# Att_steet_1.net
KiCad netlist of a schematic drawn in Altium Designer
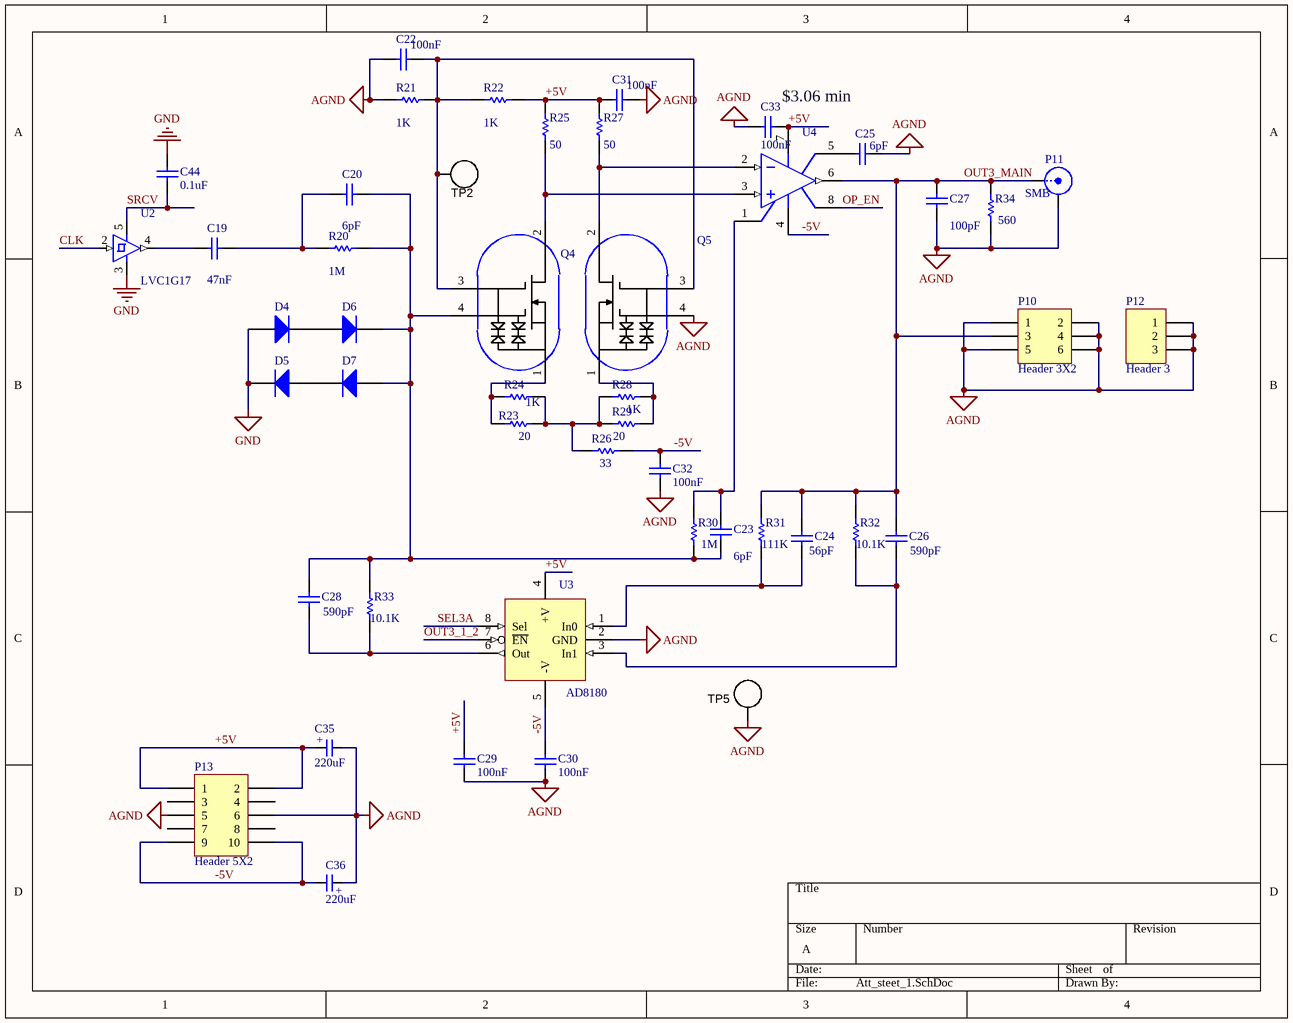
[diagram p0: Att_steet_1.SchDoc]

(export (version "E")
  (design (tool "Eeschema 10.0.6"))
  (components
    (comp (ref "C19")
      (value "47nF")
      (footprint "0805")
      (description "Ceramic Chip Capacitor - Standard")
      (fields (field (name "Comment") "C0805") (field (name "PUBLISHER") "Altium Limited"))
      (libsource (lib "KEMET Chip Capacitor") (part "C0805"))
    )
    (comp (ref "C20")
      (value "6pF")
      (footprint "0805")
      (description "Ceramic Chip Capacitor - Standard")
      (fields (field (name "Comment") "C0805") (field (name "PUBLISHER") "Altium Limited"))
      (libsource (lib "KEMET Chip Capacitor") (part "C0805"))
    )
    (comp (ref "C22")
      (value "100nF")
      (footprint "0805")
      (description "Ceramic Chip Capacitor - Standard")
      (fields (field (name "Comment") "C0805") (field (name "PUBLISHER") "Altium Limited"))
      (libsource (lib "KEMET Chip Capacitor") (part "C0805"))
    )
    (comp (ref "C23")
      (value "6pF")
      (footprint "0805")
      (description "Ceramic Chip Capacitor - Standard")
      (fields (field (name "Comment") "C0805") (field (name "PUBLISHER") "Altium Limited"))
      (libsource (lib "KEMET Chip Capacitor") (part "C0805"))
    )
    (comp (ref "C24")
      (value "56pF")
      (footprint "0805")
      (description "Ceramic Chip Capacitor - Standard")
      (fields (field (name "Comment") "C0805") (field (name "PUBLISHER") "Altium Limited"))
      (libsource (lib "KEMET Chip Capacitor") (part "C0805"))
    )
    (comp (ref "C25")
      (value "6pF")
      (footprint "C0805")
      (description "Capacitor (Semiconductor SIM Model)")
      (fields (field (name "Comment") "Cap Semi") (field (name "PUBLISHER") "Altium Limited"))
      (libsource (lib "Miscellaneous Devices") (part "Cap Semi"))
    )
    (comp (ref "C26")
      (value "590pF")
      (footprint "0805")
      (description "Ceramic Chip Capacitor - Standard")
      (fields (field (name "Comment") "C0805") (field (name "PUBLISHER") "Altium Limited"))
      (libsource (lib "KEMET Chip Capacitor") (part "C0805"))
    )
    (comp (ref "C27")
      (value "100pF")
      (footprint "0805")
      (description "Ceramic Chip Capacitor - Standard")
      (fields (field (name "Comment") "C0805") (field (name "PUBLISHER") "Altium Limited"))
      (libsource (lib "KEMET Chip Capacitor") (part "C0805"))
    )
    (comp (ref "C28")
      (value "590pF")
      (footprint "0805")
      (description "Ceramic Chip Capacitor - Standard")
      (fields (field (name "Comment") "C0805") (field (name "PUBLISHER") "Altium Limited"))
      (libsource (lib "KEMET Chip Capacitor") (part "C0805"))
    )
    (comp (ref "C29")
      (value "100nF")
      (footprint "0805")
      (description "Ceramic Chip Capacitor - Standard")
      (fields (field (name "Comment") "C0805") (field (name "PUBLISHER") "Altium Limited"))
      (libsource (lib "KEMET Chip Capacitor") (part "C0805"))
    )
    (comp (ref "C30")
      (value "100nF")
      (footprint "0805")
      (description "Ceramic Chip Capacitor - Standard")
      (fields (field (name "Comment") "C0805") (field (name "PUBLISHER") "Altium Limited"))
      (libsource (lib "KEMET Chip Capacitor") (part "C0805"))
    )
    (comp (ref "C31")
      (value "100nF")
      (footprint "0805")
      (description "Ceramic Chip Capacitor - Standard")
      (fields (field (name "Comment") "C0805") (field (name "PUBLISHER") "Altium Limited"))
      (libsource (lib "KEMET Chip Capacitor") (part "C0805"))
    )
    (comp (ref "C32")
      (value "100nF")
      (footprint "0805")
      (description "Ceramic Chip Capacitor - Standard")
      (fields (field (name "Comment") "C0805") (field (name "PUBLISHER") "Altium Limited"))
      (libsource (lib "KEMET Chip Capacitor") (part "C0805"))
    )
    (comp (ref "C33")
      (value "100nF")
      (footprint "0805")
      (description "Ceramic Chip Capacitor - Standard")
      (fields (field (name "Comment") "C0805") (field (name "PUBLISHER") "Altium Limited"))
      (libsource (lib "KEMET Chip Capacitor") (part "C0805"))
    )
    (comp (ref "C35")
      (value "220uF")
      (footprint "Scope:H13")
      (fields (field (name "MANUFACTURER") "Panasonic") (field (name "Comment") "Cap"))
      (libsource (lib "Scope") (part "Lyt Cap"))
    )
    (comp (ref "C36")
      (value "220uF")
      (footprint "Scope:H13")
      (fields (field (name "MANUFACTURER") "Panasonic") (field (name "Comment") "Cap"))
      (libsource (lib "Scope") (part "Lyt Cap"))
    )
    (comp (ref "C44")
      (value "0.1uF")
      (footprint "C0805")
      (description "Capacitor")
      (fields (field (name "Comment") "Cap") (field (name "PUBLISHER") "Altium Limited"))
      (libsource (lib "Miscellaneous Devices") (part "Cap"))
    )
    (comp (ref "D4")
      (value "Diode BAS21")
      (footprint "SOT95P240-3N")
      (description "Silicon Switching Diode for High-Speed, High-Voltage Switching")
      (fields (field (name "PUBLISHER") "Altium Limited"))
      (libsource (lib "Miscellaneous Devices") (part "Diode BAS21"))
    )
    (comp (ref "D5")
      (value "Diode BAS21")
      (footprint "SOT95P240-3N")
      (description "Silicon Switching Diode for High-Speed, High-Voltage Switching")
      (fields (field (name "PUBLISHER") "Altium Limited"))
      (libsource (lib "Miscellaneous Devices") (part "Diode BAS21"))
    )
    (comp (ref "D6")
      (value "Diode BAS21")
      (footprint "SOT95P240-3N")
      (description "Silicon Switching Diode for High-Speed, High-Voltage Switching")
      (fields (field (name "PUBLISHER") "Altium Limited"))
      (libsource (lib "Miscellaneous Devices") (part "Diode BAS21"))
    )
    (comp (ref "D7")
      (value "Diode BAS21")
      (footprint "SOT95P240-3N")
      (description "Silicon Switching Diode for High-Speed, High-Voltage Switching")
      (fields (field (name "PUBLISHER") "Altium Limited"))
      (libsource (lib "Miscellaneous Devices") (part "Diode BAS21"))
    )
    (comp (ref "P10")
      (value "Header 3X2")
      (footprint "HDR2X3")
      (description "Header, 3-Pin, Dual row")
      (fields (field (name "PUBLISHER") "Altium Limited"))
      (libsource (lib "Miscellaneous Connectors") (part "Header 3X2"))
    )
    (comp (ref "P11")
      (value "SMB")
      (footprint "SMB_V-RJ45")
      (description "SMB Straight Connector")
      (fields (field (name "PUBLISHER") "Altium Limited"))
      (libsource (lib "Miscellaneous Connectors") (part "SMB"))
    )
    (comp (ref "P12")
      (value "Header 3")
      (footprint "HDR1X3")
      (description "Header, 3-Pin")
      (fields (field (name "PUBLISHER") "Altium Limited"))
      (libsource (lib "Miscellaneous Connectors") (part "Header 3"))
    )
    (comp (ref "P13")
      (value "Header 5X2")
      (footprint "HDR2X5")
      (description "Header, 5-Pin, Dual row")
      (fields (field (name "PUBLISHER") "Altium Limited"))
      (libsource (lib "Miscellaneous Connectors") (part "Header 5X2"))
    )
    (comp (ref "Q4")
      (value "MOSFET")
      (footprint "Scope:SOT143")
      (description "Dual-gate MOSFET")
      (fields (field (name "MANUFACTURER") "NXP"))
      (libsource (lib "") (part "BF998_1"))
    )
    (comp (ref "Q5")
      (value "MOSFET")
      (footprint "Scope:SOT143")
      (description "Dual-gate MOSFET")
      (fields (field (name "MANUFACTURER") "NXP"))
      (libsource (lib "Scope") (part "BF998"))
    )
    (comp (ref "R20")
      (value "1M")
      (footprint "0805")
      (fields (field (name "Comment") "ERA6Y") (field (name "PUBLISHER") "Altium Limited"))
      (libsource (lib "Panasonic Resistor") (part "ERA6Y"))
    )
    (comp (ref "R21")
      (value "1K")
      (footprint "0805")
      (fields (field (name "Comment") "ERA6Y") (field (name "PUBLISHER") "Altium Limited"))
      (libsource (lib "Panasonic Resistor") (part "ERA6Y"))
    )
    (comp (ref "R22")
      (value "1K")
      (footprint "0805")
      (fields (field (name "Comment") "ERA6Y") (field (name "PUBLISHER") "Altium Limited"))
      (libsource (lib "Panasonic Resistor") (part "ERA6Y"))
    )
    (comp (ref "R23")
      (value "20")
      (footprint "0805")
      (fields (field (name "Comment") "ERA6Y") (field (name "PUBLISHER") "Altium Limited"))
      (libsource (lib "Panasonic Resistor") (part "ERA6Y"))
    )
    (comp (ref "R24")
      (value "1K")
      (footprint "0805")
      (fields (field (name "Comment") "ERA6Y") (field (name "PUBLISHER") "Altium Limited"))
      (libsource (lib "Panasonic Resistor") (part "ERA6Y"))
    )
    (comp (ref "R25")
      (value "50")
      (footprint "0805")
      (fields (field (name "Comment") "ERA6Y") (field (name "PUBLISHER") "Altium Limited"))
      (libsource (lib "Panasonic Resistor") (part "ERA6Y"))
    )
    (comp (ref "R26")
      (value "33")
      (footprint "0805")
      (fields (field (name "Comment") "ERA6Y") (field (name "PUBLISHER") "Altium Limited"))
      (libsource (lib "Panasonic Resistor") (part "ERA6Y"))
    )
    (comp (ref "R27")
      (value "50")
      (footprint "0805")
      (fields (field (name "Comment") "ERA6Y") (field (name "PUBLISHER") "Altium Limited"))
      (libsource (lib "Panasonic Resistor") (part "ERA6Y"))
    )
    (comp (ref "R28")
      (value "1K")
      (footprint "0805")
      (fields (field (name "Comment") "ERA6Y") (field (name "PUBLISHER") "Altium Limited"))
      (libsource (lib "Panasonic Resistor") (part "ERA6Y"))
    )
    (comp (ref "R29")
      (value "20")
      (footprint "0805")
      (fields (field (name "Comment") "ERA6Y") (field (name "PUBLISHER") "Altium Limited"))
      (libsource (lib "Panasonic Resistor") (part "ERA6Y"))
    )
    (comp (ref "R30")
      (value "1M")
      (footprint "0805")
      (fields (field (name "Comment") "ERA6Y") (field (name "PUBLISHER") "Altium Limited"))
      (libsource (lib "Panasonic Resistor") (part "ERA6Y"))
    )
    (comp (ref "R31")
      (value "111K")
      (footprint "0805")
      (fields (field (name "Comment") "ERA6Y") (field (name "PUBLISHER") "Altium Limited"))
      (libsource (lib "Panasonic Resistor") (part "ERA6Y"))
    )
    (comp (ref "R32")
      (value "10.1K")
      (footprint "0805")
      (fields (field (name "Comment") "ERA6Y") (field (name "PUBLISHER") "Altium Limited"))
      (libsource (lib "Panasonic Resistor") (part "ERA6Y"))
    )
    (comp (ref "R33")
      (value "10.1K")
      (footprint "0805")
      (fields (field (name "Comment") "ERA6Y") (field (name "PUBLISHER") "Altium Limited"))
      (libsource (lib "Panasonic Resistor") (part "ERA6Y"))
    )
    (comp (ref "R34")
      (value "560")
      (footprint "0805")
      (fields (field (name "Comment") "ERA6Y") (field (name "PUBLISHER") "Altium Limited"))
      (libsource (lib "Panasonic Resistor") (part "ERA6Y"))
    )
    (comp (ref "TP2")
      (value "TESTPOINT")
      (footprint "TESTPOINT")
      (description "TEST POINT.  No entry in BOM.")
      (libsource (lib "NSC MiscParts") (part "TESTPOINT"))
    )
    (comp (ref "TP5")
      (value "TESTPOINT")
      (footprint "TESTPOINT")
      (description "TEST POINT.  No entry in BOM.")
      (libsource (lib "NSC MiscParts") (part "TESTPOINT"))
    )
    (comp (ref "U2")
      (value "LVC1G17")
      (footprint "SC_70_5")
      (fields
        (field (name "MANUFACTURER") "Texas Instruments")
        (field (name "MANUFACTURER PART NUMBER") "SN74LVC1G17DCKR")
        (field (name "Comment") "SN74LVC1G17")
      )
      (libsource (lib "VIVENG_Library") (part "SN74LVC1G17"))
    )
    (comp (ref "U3")
      (value "AD8180")
      (footprint "SOIC127P600-8AL")
      (fields (field (name "PARTNUMBER") "AD8180"))
      (libsource (lib "Scope") (part "AD8180"))
    )
    (comp (ref "U4")
      (value "AD707AR")
      (footprint "SO-8_N")
      (description "Ultra-Low Drift Operational Amplifier")
      (fields (field (name "PARTNUMBER") "AD8099") (field (name "PUBLISHER") "Altium Limited"))
      (libsource (lib "AD Operational Amplifier") (part "AD707AR"))
    )
  )
  (nets
    (net (code "1") (name "/+5V") (class "Default")
      (node (ref "C29") (pin "1") (pinfunction "1_1") (pintype "passive"))
      (node (ref "C31") (pin "1") (pinfunction "1_1") (pintype "passive"))
      (node (ref "C33") (pin "1") (pinfunction "1_1") (pintype "passive"))
      (node (ref "C35") (pin "1") (pinfunction "1_1") (pintype "passive"))
      (node (ref "P13") (pin "1") (pinfunction "1_1") (pintype "passive"))
      (node (ref "P13") (pin "2") (pinfunction "2_2") (pintype "passive"))
      (node (ref "R22") (pin "1") (pinfunction "1_1") (pintype "passive"))
      (node (ref "R25") (pin "1") (pinfunction "1_1") (pintype "passive"))
      (node (ref "R27") (pin "1") (pinfunction "1_1") (pintype "passive"))
      (node (ref "U3") (pin "4") (pinfunction "+V_4") (pintype "power_in"))
      (node (ref "U4") (pin "7") (pinfunction "V+_7") (pintype "power_in"))
    )
    (net (code "2") (name "/-5V") (class "Default")
      (node (ref "C30") (pin "1") (pinfunction "1_1") (pintype "passive"))
      (node (ref "C32") (pin "2") (pinfunction "2_2") (pintype "passive"))
      (node (ref "C36") (pin "2") (pinfunction "2_2") (pintype "passive"))
      (node (ref "P13") (pin "10") (pinfunction "10_10") (pintype "passive"))
      (node (ref "P13") (pin "9") (pinfunction "9_9") (pintype "passive"))
      (node (ref "R26") (pin "1") (pinfunction "1_1") (pintype "passive"))
      (node (ref "U3") (pin "5") (pinfunction "-V_5") (pintype "power_in"))
      (node (ref "U4") (pin "4") (pinfunction "V-_4") (pintype "power_in"))
    )
    (net (code "3") (name "/CLK") (class "Default")
      (node (ref "U2") (pin "2") (pinfunction "1A_2") (pintype "input"))
    )
    (net (code "4") (name "/OP_EN") (class "Default")
      (node (ref "U4") (pin "8") (pinfunction "NULL2_8") (pintype "passive"))
    )
    (net (code "5") (name "/OUT3_1_2") (class "Default")
      (node (ref "U3") (pin "7") (pinfunction "~{EN}_7") (pintype "input"))
    )
    (net (code "6") (name "/OUT3_MAIN") (class "Default")
      (node (ref "C24") (pin "2") (pinfunction "2_2") (pintype "passive"))
      (node (ref "C26") (pin "2") (pinfunction "2_2") (pintype "passive"))
      (node (ref "C27") (pin "2") (pinfunction "2_2") (pintype "passive"))
      (node (ref "P10") (pin "3") (pinfunction "3_3") (pintype "passive"))
      (node (ref "P11") (pin "1") (pinfunction "X_1") (pintype "passive"))
      (node (ref "R31") (pin "2") (pinfunction "2_2") (pintype "passive"))
      (node (ref "R32") (pin "2") (pinfunction "2_2") (pintype "passive"))
      (node (ref "R34") (pin "2") (pinfunction "2_2") (pintype "passive"))
      (node (ref "U4") (pin "6") (pinfunction "OUT_6") (pintype "output"))
    )
    (net (code "7") (name "/SEL3A") (class "Default")
      (node (ref "U3") (pin "8") (pinfunction "Sel_8") (pintype "input"))
    )
    (net (code "8") (name "/SRCV") (class "Default")
      (node (ref "C44") (pin "1") (pinfunction "1_1") (pintype "passive"))
      (node (ref "U2") (pin "5") (pinfunction "VCC_5") (pintype "power_in"))
    )
    (net (code "9") (name "AGND") (class "Default")
      (node (ref "C22") (pin "1") (pinfunction "1_1") (pintype "passive"))
      (node (ref "C25") (pin "2") (pinfunction "2_2") (pintype "passive"))
      (node (ref "C27") (pin "1") (pinfunction "1_1") (pintype "passive"))
      (node (ref "C29") (pin "2") (pinfunction "2_2") (pintype "passive"))
      (node (ref "C30") (pin "2") (pinfunction "2_2") (pintype "passive"))
      (node (ref "C31") (pin "2") (pinfunction "2_2") (pintype "passive"))
      (node (ref "C32") (pin "1") (pinfunction "1_1") (pintype "passive"))
      (node (ref "C33") (pin "2") (pinfunction "2_2") (pintype "passive"))
      (node (ref "C35") (pin "2") (pinfunction "2_2") (pintype "passive"))
      (node (ref "C36") (pin "1") (pinfunction "1_1") (pintype "passive"))
      (node (ref "P10") (pin "1") (pinfunction "1_1") (pintype "passive"))
      (node (ref "P10") (pin "2") (pinfunction "2_2") (pintype "passive"))
      (node (ref "P10") (pin "4") (pinfunction "4_4") (pintype "passive"))
      (node (ref "P10") (pin "5") (pinfunction "5_5") (pintype "passive"))
      (node (ref "P10") (pin "6") (pinfunction "6_6") (pintype "passive"))
      (node (ref "P11") (pin "2") (pinfunction "Y_2") (pintype "passive"))
      (node (ref "P12") (pin "1") (pinfunction "1_1") (pintype "passive"))
      (node (ref "P12") (pin "2") (pinfunction "2_2") (pintype "passive"))
      (node (ref "P12") (pin "3") (pinfunction "3_3") (pintype "passive"))
      (node (ref "P13") (pin "5") (pinfunction "5_5") (pintype "passive"))
      (node (ref "P13") (pin "6") (pinfunction "6_6") (pintype "passive"))
      (node (ref "Q5") (pin "4") (pinfunction "4_4") (pintype "passive"))
      (node (ref "R21") (pin "2") (pinfunction "2_2") (pintype "passive"))
      (node (ref "R34") (pin "1") (pinfunction "1_1") (pintype "passive"))
      (node (ref "TP5") (pin "1") (pintype "passive"))
      (node (ref "U3") (pin "2") (pinfunction "GND_2") (pintype "power_in"))
    )
    (net (code "10") (name "GND") (class "Default")
      (node (ref "C44") (pin "2") (pinfunction "2_2") (pintype "passive"))
      (node (ref "D4") (pin "1") (pinfunction "A_1") (pintype "passive"))
      (node (ref "D5") (pin "3") (pinfunction "K_3") (pintype "passive"))
      (node (ref "U2") (pin "3") (pinfunction "GND_3") (pintype "power_in"))
    )
    (net (code "11") (name "Net-(C19-Pad2)") (class "Default")
      (node (ref "C19") (pin "2") (pinfunction "2_2") (pintype "passive"))
      (node (ref "C20") (pin "1") (pinfunction "1_1") (pintype "passive"))
      (node (ref "R20") (pin "2") (pinfunction "2_2") (pintype "passive"))
    )
    (net (code "12") (name "Net-(C22-Pad2)") (class "Default")
      (node (ref "C22") (pin "2") (pinfunction "2_2") (pintype "passive"))
      (node (ref "Q4") (pin "3") (pinfunction "3_3") (pintype "passive"))
      (node (ref "Q5") (pin "3") (pinfunction "3_3") (pintype "passive"))
      (node (ref "R21") (pin "1") (pinfunction "1_1") (pintype "passive"))
      (node (ref "R22") (pin "2") (pinfunction "2_2") (pintype "passive"))
      (node (ref "TP2") (pin "1") (pintype "passive"))
    )
    (net (code "13") (name "Net-(D4-K)") (class "Default")
      (node (ref "D4") (pin "3") (pinfunction "K_3") (pintype "passive"))
      (node (ref "D6") (pin "1") (pinfunction "A_1") (pintype "passive"))
    )
    (net (code "14") (name "Net-(D5-A)") (class "Default")
      (node (ref "D5") (pin "1") (pinfunction "A_1") (pintype "passive"))
      (node (ref "D7") (pin "3") (pinfunction "K_3") (pintype "passive"))
    )
    (net (code "15") (name "Net-(D6-K)") (class "Default")
      (node (ref "C20") (pin "2") (pinfunction "2_2") (pintype "passive"))
      (node (ref "C23") (pin "1") (pinfunction "1_1") (pintype "passive"))
      (node (ref "C28") (pin "2") (pinfunction "2_2") (pintype "passive"))
      (node (ref "D6") (pin "3") (pinfunction "K_3") (pintype "passive"))
      (node (ref "D7") (pin "1") (pinfunction "A_1") (pintype "passive"))
      (node (ref "Q4") (pin "4") (pinfunction "4_4") (pintype "passive"))
      (node (ref "R20") (pin "1") (pinfunction "1_1") (pintype "passive"))
      (node (ref "R30") (pin "1") (pinfunction "1_1") (pintype "passive"))
      (node (ref "R33") (pin "2") (pinfunction "2_2") (pintype "passive"))
    )
    (net (code "16") (name "Net-(Q4-Pad1)") (class "Default")
      (node (ref "Q4") (pin "1") (pinfunction "1_1") (pintype "passive"))
      (node (ref "R23") (pin "2") (pinfunction "2_2") (pintype "passive"))
      (node (ref "R24") (pin "2") (pinfunction "2_2") (pintype "passive"))
    )
    (net (code "17") (name "Net-(Q5-Pad1)") (class "Default")
      (node (ref "Q5") (pin "1") (pinfunction "1_1") (pintype "passive"))
      (node (ref "R28") (pin "1") (pinfunction "1_1") (pintype "passive"))
      (node (ref "R29") (pin "1") (pinfunction "1_1") (pintype "passive"))
    )
    (net (code "18") (name "Net-(R23-Pad1)") (class "Default")
      (node (ref "R23") (pin "1") (pinfunction "1_1") (pintype "passive"))
      (node (ref "R24") (pin "1") (pinfunction "1_1") (pintype "passive"))
      (node (ref "R26") (pin "2") (pinfunction "2_2") (pintype "passive"))
      (node (ref "R28") (pin "2") (pinfunction "2_2") (pintype "passive"))
      (node (ref "R29") (pin "2") (pinfunction "2_2") (pintype "passive"))
    )
    (net (code "19") (name "Net-(U2-1Y)") (class "Default")
      (node (ref "C19") (pin "1") (pinfunction "1_1") (pintype "passive"))
      (node (ref "U2") (pin "4") (pinfunction "1Y_4") (pintype "output"))
    )
    (net (code "20") (name "Net-(U3-In0)") (class "Default")
      (node (ref "C24") (pin "1") (pinfunction "1_1") (pintype "passive"))
      (node (ref "R31") (pin "1") (pinfunction "1_1") (pintype "passive"))
      (node (ref "U3") (pin "1") (pinfunction "In0_1") (pintype "input"))
    )
    (net (code "21") (name "Net-(U3-In1)") (class "Default")
      (node (ref "C26") (pin "1") (pinfunction "1_1") (pintype "passive"))
      (node (ref "R32") (pin "1") (pinfunction "1_1") (pintype "passive"))
      (node (ref "U3") (pin "3") (pinfunction "In1_3") (pintype "input"))
    )
    (net (code "22") (name "Net-(U3-Out)") (class "Default")
      (node (ref "C28") (pin "1") (pinfunction "1_1") (pintype "passive"))
      (node (ref "R33") (pin "1") (pinfunction "1_1") (pintype "passive"))
      (node (ref "U3") (pin "6") (pinfunction "Out_6") (pintype "output"))
    )
    (net (code "23") (name "Net-(U4-IN+)") (class "Default")
      (node (ref "Q4") (pin "2") (pinfunction "2_2") (pintype "passive"))
      (node (ref "R25") (pin "2") (pinfunction "2_2") (pintype "passive"))
      (node (ref "U4") (pin "3") (pinfunction "IN+_3") (pintype "input"))
    )
    (net (code "24") (name "Net-(U4-IN-)") (class "Default")
      (node (ref "Q5") (pin "2") (pinfunction "2_2") (pintype "passive"))
      (node (ref "R27") (pin "2") (pinfunction "2_2") (pintype "passive"))
      (node (ref "U4") (pin "2") (pinfunction "IN-_2") (pintype "input"))
    )
    (net (code "25") (name "Net-(U4-NC)") (class "Default")
      (node (ref "C25") (pin "1") (pinfunction "1_1") (pintype "passive"))
      (node (ref "U4") (pin "5") (pinfunction "NC_5") (pintype "passive"))
    )
    (net (code "26") (name "Net-(U4-NULL1)") (class "Default")
      (node (ref "C23") (pin "2") (pinfunction "2_2") (pintype "passive"))
      (node (ref "R30") (pin "2") (pinfunction "2_2") (pintype "passive"))
      (node (ref "U4") (pin "1") (pinfunction "NULL1_1") (pintype "passive"))
    )
    (net (code "27") (name "unconnected-(P13-Pad3)") (class "Default")
      (node (ref "P13") (pin "3") (pinfunction "3_3") (pintype "passive"))
    )
    (net (code "28") (name "unconnected-(P13-Pad4)") (class "Default")
      (node (ref "P13") (pin "4") (pinfunction "4_4") (pintype "passive"))
    )
    (net (code "29") (name "unconnected-(P13-Pad7)") (class "Default")
      (node (ref "P13") (pin "7") (pinfunction "7_7") (pintype "passive"))
    )
    (net (code "30") (name "unconnected-(P13-Pad8)") (class "Default")
      (node (ref "P13") (pin "8") (pinfunction "8_8") (pintype "passive"))
    )
  )
)
